# I2C_Messenger_r2.net
KiCad netlist of a schematic drawn in EAGLE
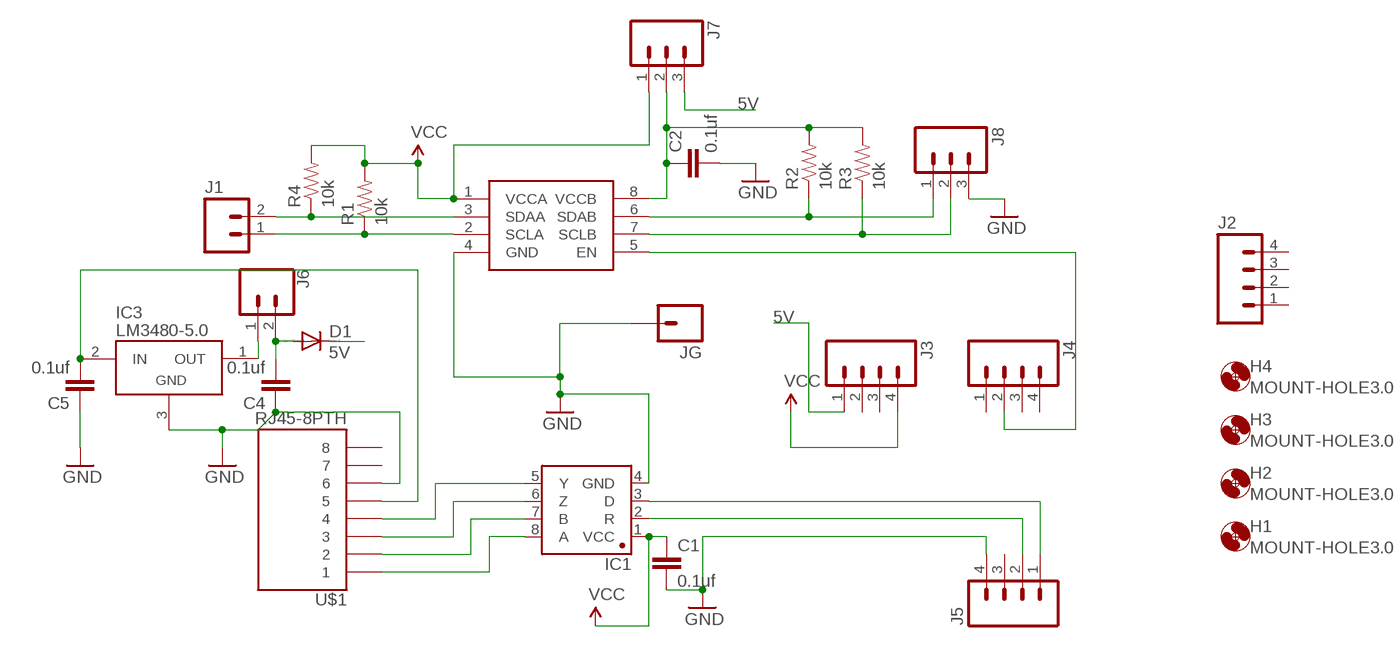
[diagram p0: schematic, sheet 1]

(export (version "E")
  (design (tool "Eeschema 10.0.6"))
  (components
    (comp (ref "C1")
      (value "0.1uf")
      (footprint "eagle-import:1206")
      (libsource (lib "eagle-import") (part "CAP1206"))
    )
    (comp (ref "C2")
      (value "0.1uf")
      (footprint "eagle-import:1206")
      (libsource (lib "eagle-import") (part "CAP1206"))
    )
    (comp (ref "C4")
      (value "0.1uf")
      (footprint "eagle-import:1206")
      (libsource (lib "eagle-import") (part "CAP1206"))
    )
    (comp (ref "C5")
      (value "0.1uf")
      (footprint "eagle-import:1206")
      (libsource (lib "eagle-import") (part "CAP1206"))
    )
    (comp (ref "D1")
      (value "MBR0520LT")
      (footprint "eagle-import:SOD123")
      (libsource (lib "eagle-import") (part "MBR0520LT"))
    )
    (comp (ref "H1")
      (value "MOUNT-HOLE3.0")
      (footprint "eagle-import:3,0")
      (libsource (lib "eagle-import") (part "MOUNT-HOLE3.0"))
    )
    (comp (ref "H2")
      (value "MOUNT-HOLE3.0")
      (footprint "eagle-import:3,0")
      (libsource (lib "eagle-import") (part "MOUNT-HOLE3.0"))
    )
    (comp (ref "H3")
      (value "MOUNT-HOLE3.0")
      (footprint "eagle-import:3,0")
      (libsource (lib "eagle-import") (part "MOUNT-HOLE3.0"))
    )
    (comp (ref "H4")
      (value "MOUNT-HOLE3.0")
      (footprint "eagle-import:3,0")
      (libsource (lib "eagle-import") (part "MOUNT-HOLE3.0"))
    )
    (comp (ref "IC1")
      (value "SN65HVD31DR")
      (footprint "eagle-import:SO08")
      (libsource (lib "eagle-import") (part "SN65HVD31DR"))
    )
    (comp (ref "IC2")
      (value "PCA9517")
      (footprint "eagle-import:SO-08")
      (libsource (lib "eagle-import") (part "PCA9517"))
    )
    (comp (ref "IC3")
      (value "LM3480-5.0")
      (footprint "eagle-import:SOT-23-3")
      (libsource (lib "eagle-import") (part "LM3480-5.0"))
    )
    (comp (ref "J1")
      (value "M02PTH")
      (footprint "eagle-import:1X02@1")
      (libsource (lib "eagle-import") (part "M02PTH"))
    )
    (comp (ref "J2")
      (value "M04PTH")
      (footprint "eagle-import:1X04")
      (libsource (lib "eagle-import") (part "M04PTH"))
    )
    (comp (ref "J3")
      (value "M04PTH")
      (footprint "eagle-import:1X04")
      (libsource (lib "eagle-import") (part "M04PTH"))
    )
    (comp (ref "J4")
      (value "M04PTH")
      (footprint "eagle-import:1X04")
      (libsource (lib "eagle-import") (part "M04PTH"))
    )
    (comp (ref "J5")
      (value "M04PTH")
      (footprint "eagle-import:1X04")
      (libsource (lib "eagle-import") (part "M04PTH"))
    )
    (comp (ref "J6")
      (value "CONN_02")
      (footprint "eagle-import:1X02")
      (libsource (lib "eagle-import") (part "CONN_02"))
    )
    (comp (ref "J7")
      (value "M03PTH")
      (footprint "eagle-import:1X03")
      (libsource (lib "eagle-import") (part "M03PTH"))
    )
    (comp (ref "J8")
      (value "M03SCREW_LOCK")
      (footprint "eagle-import:SCREWTERMINAL-3.5MM-3_LOCK.007S")
      (libsource (lib "eagle-import") (part "M03SCREW_LOCK"))
    )
    (comp (ref "JG")
      (value "M01PTH")
      (footprint "eagle-import:1X01")
      (libsource (lib "eagle-import") (part "M01PTH"))
    )
    (comp (ref "R1")
      (value "10k")
      (footprint "eagle-import:1206")
      (libsource (lib "eagle-import") (part "RESISTOR1206"))
    )
    (comp (ref "R2")
      (value "10k")
      (footprint "eagle-import:1206")
      (libsource (lib "eagle-import") (part "RESISTOR1206"))
    )
    (comp (ref "R3")
      (value "10k")
      (footprint "eagle-import:1206")
      (libsource (lib "eagle-import") (part "RESISTOR1206"))
    )
    (comp (ref "R4")
      (value "10k")
      (footprint "eagle-import:1206")
      (libsource (lib "eagle-import") (part "RESISTOR1206"))
    )
    (comp (ref "U$1")
      (value "RJ45-8PTH")
      (footprint "eagle-import:RJ45-8")
      (libsource (lib "eagle-import") (part "RJ45-8PTH"))
    )
  )
  (nets
    (net (code "1") (name "/5V") (class "Default")
      (node (ref "D1") (pin "C") (pinfunction "C_C") (pintype "passive"))
      (node (ref "J3") (pin "1") (pinfunction "1_1") (pintype "passive"))
      (node (ref "J7") (pin "3") (pinfunction "3_3") (pintype "passive"))
    )
    (net (code "2") (name "GND") (class "Default")
      (node (ref "C1") (pin "2") (pinfunction "2_2") (pintype "passive"))
      (node (ref "C2") (pin "2") (pinfunction "2_2") (pintype "passive"))
      (node (ref "C4") (pin "1") (pinfunction "1_1") (pintype "passive"))
      (node (ref "C5") (pin "1") (pinfunction "1_1") (pintype "passive"))
      (node (ref "IC1") (pin "4") (pinfunction "GND_4") (pintype "bidirectional"))
      (node (ref "IC2") (pin "4") (pinfunction "GND_4") (pintype "bidirectional"))
      (node (ref "IC3") (pin "3") (pinfunction "GND_3") (pintype "power_in"))
      (node (ref "J5") (pin "4") (pinfunction "4_4") (pintype "passive"))
      (node (ref "J8") (pin "3") (pinfunction "3_3") (pintype "passive"))
      (node (ref "JG") (pin "1") (pinfunction "1_1") (pintype "passive"))
      (node (ref "U$1") (pin "6") (pinfunction "6_6") (pintype "bidirectional"))
    )
    (net (code "3") (name "Net-(C4-Pad2)") (class "Default")
      (node (ref "C4") (pin "2") (pinfunction "2_2") (pintype "passive"))
      (node (ref "D1") (pin "A") (pinfunction "A_A") (pintype "passive"))
      (node (ref "J6") (pin "2") (pinfunction "2_2") (pintype "passive"))
    )
    (net (code "4") (name "Net-(IC1-A)") (class "Default")
      (node (ref "IC1") (pin "8") (pinfunction "A_8") (pintype "bidirectional"))
      (node (ref "U$1") (pin "1") (pinfunction "1_1") (pintype "bidirectional"))
    )
    (net (code "5") (name "Net-(IC1-B)") (class "Default")
      (node (ref "IC1") (pin "7") (pinfunction "B_7") (pintype "bidirectional"))
      (node (ref "U$1") (pin "2") (pinfunction "2_2") (pintype "bidirectional"))
    )
    (net (code "6") (name "Net-(IC1-D)") (class "Default")
      (node (ref "IC1") (pin "3") (pinfunction "D_3") (pintype "bidirectional"))
      (node (ref "J5") (pin "1") (pinfunction "1_1") (pintype "passive"))
    )
    (net (code "7") (name "Net-(IC1-R)") (class "Default")
      (node (ref "IC1") (pin "2") (pinfunction "R_2") (pintype "bidirectional"))
      (node (ref "J5") (pin "2") (pinfunction "2_2") (pintype "passive"))
    )
    (net (code "8") (name "Net-(IC1-Y)") (class "Default")
      (node (ref "IC1") (pin "5") (pinfunction "Y_5") (pintype "bidirectional"))
      (node (ref "U$1") (pin "4") (pinfunction "4_4") (pintype "bidirectional"))
    )
    (net (code "9") (name "Net-(IC1-Z)") (class "Default")
      (node (ref "IC1") (pin "6") (pinfunction "Z_6") (pintype "bidirectional"))
      (node (ref "U$1") (pin "3") (pinfunction "3_3") (pintype "bidirectional"))
    )
    (net (code "10") (name "Net-(IC2-EN)") (class "Default")
      (node (ref "IC2") (pin "5") (pinfunction "EN_5") (pintype "bidirectional"))
      (node (ref "J4") (pin "2") (pinfunction "2_2") (pintype "passive"))
    )
    (net (code "11") (name "Net-(IC2-SCLA)") (class "Default")
      (node (ref "IC2") (pin "2") (pinfunction "SCLA_2") (pintype "bidirectional"))
      (node (ref "J1") (pin "1") (pinfunction "1_1") (pintype "passive"))
      (node (ref "R1") (pin "1") (pinfunction "1_1") (pintype "passive"))
    )
    (net (code "12") (name "Net-(IC2-SCLB)") (class "Default")
      (node (ref "IC2") (pin "7") (pinfunction "SCLB_7") (pintype "bidirectional"))
      (node (ref "J8") (pin "2") (pinfunction "2_2") (pintype "passive"))
      (node (ref "R3") (pin "1") (pinfunction "1_1") (pintype "passive"))
    )
    (net (code "13") (name "Net-(IC2-SDAA)") (class "Default")
      (node (ref "IC2") (pin "3") (pinfunction "SDAA_3") (pintype "bidirectional"))
      (node (ref "J1") (pin "2") (pinfunction "2_2") (pintype "passive"))
      (node (ref "R4") (pin "1") (pinfunction "1_1") (pintype "passive"))
    )
    (net (code "14") (name "Net-(IC2-SDAB)") (class "Default")
      (node (ref "IC2") (pin "6") (pinfunction "SDAB_6") (pintype "bidirectional"))
      (node (ref "J8") (pin "1") (pinfunction "1_1") (pintype "passive"))
      (node (ref "R2") (pin "1") (pinfunction "1_1") (pintype "passive"))
    )
    (net (code "15") (name "Net-(IC2-VCCB)") (class "Default")
      (node (ref "C2") (pin "1") (pinfunction "1_1") (pintype "passive"))
      (node (ref "IC2") (pin "8") (pinfunction "VCCB_8") (pintype "bidirectional"))
      (node (ref "J7") (pin "2") (pinfunction "2_2") (pintype "passive"))
      (node (ref "R2") (pin "2") (pinfunction "2_2") (pintype "passive"))
      (node (ref "R3") (pin "2") (pinfunction "2_2") (pintype "passive"))
    )
    (net (code "16") (name "Net-(IC3-IN)") (class "Default")
      (node (ref "C5") (pin "2") (pinfunction "2_2") (pintype "passive"))
      (node (ref "IC3") (pin "2") (pinfunction "IN_2") (pintype "power_in"))
      (node (ref "U$1") (pin "5") (pinfunction "5_5") (pintype "bidirectional"))
    )
    (net (code "17") (name "Net-(IC3-OUT)") (class "Default")
      (node (ref "IC3") (pin "1") (pinfunction "OUT_1") (pintype "power_in"))
      (node (ref "J6") (pin "1") (pinfunction "1_1") (pintype "passive"))
    )
    (net (code "18") (name "VCC") (class "Default")
      (node (ref "C1") (pin "1") (pinfunction "1_1") (pintype "passive"))
      (node (ref "IC1") (pin "1") (pinfunction "VCC_1") (pintype "bidirectional"))
      (node (ref "IC2") (pin "1") (pinfunction "VCCA_1") (pintype "bidirectional"))
      (node (ref "J3") (pin "4") (pinfunction "4_4") (pintype "passive"))
      (node (ref "J7") (pin "1") (pinfunction "1_1") (pintype "passive"))
      (node (ref "R1") (pin "2") (pinfunction "2_2") (pintype "passive"))
      (node (ref "R4") (pin "2") (pinfunction "2_2") (pintype "passive"))
    )
    (net (code "19") (name "unconnected-(J2-Pad1)") (class "Default")
      (node (ref "J2") (pin "1") (pinfunction "1_1") (pintype "passive"))
    )
    (net (code "20") (name "unconnected-(J2-Pad2)") (class "Default")
      (node (ref "J2") (pin "2") (pinfunction "2_2") (pintype "passive"))
    )
    (net (code "21") (name "unconnected-(J2-Pad3)") (class "Default")
      (node (ref "J2") (pin "3") (pinfunction "3_3") (pintype "passive"))
    )
    (net (code "22") (name "unconnected-(J2-Pad4)") (class "Default")
      (node (ref "J2") (pin "4") (pinfunction "4_4") (pintype "passive"))
    )
    (net (code "23") (name "unconnected-(J3-Pad2)") (class "Default")
      (node (ref "J3") (pin "2") (pinfunction "2_2") (pintype "passive"))
    )
    (net (code "24") (name "unconnected-(J3-Pad3)") (class "Default")
      (node (ref "J3") (pin "3") (pinfunction "3_3") (pintype "passive"))
    )
    (net (code "25") (name "unconnected-(J4-Pad1)") (class "Default")
      (node (ref "J4") (pin "1") (pinfunction "1_1") (pintype "passive"))
    )
    (net (code "26") (name "unconnected-(J4-Pad3)") (class "Default")
      (node (ref "J4") (pin "3") (pinfunction "3_3") (pintype "passive"))
    )
    (net (code "27") (name "unconnected-(J4-Pad4)") (class "Default")
      (node (ref "J4") (pin "4") (pinfunction "4_4") (pintype "passive"))
    )
    (net (code "28") (name "unconnected-(J5-Pad3)") (class "Default")
      (node (ref "J5") (pin "3") (pinfunction "3_3") (pintype "passive"))
    )
    (net (code "29") (name "unconnected-(U$1-Pad7)") (class "Default")
      (node (ref "U$1") (pin "7") (pinfunction "7_7") (pintype "bidirectional"))
    )
    (net (code "30") (name "unconnected-(U$1-Pad8)") (class "Default")
      (node (ref "U$1") (pin "8") (pinfunction "8_8") (pintype "bidirectional"))
    )
  )
)
